# top.net
KiCad netlist of a schematic drawn in Altium Designer
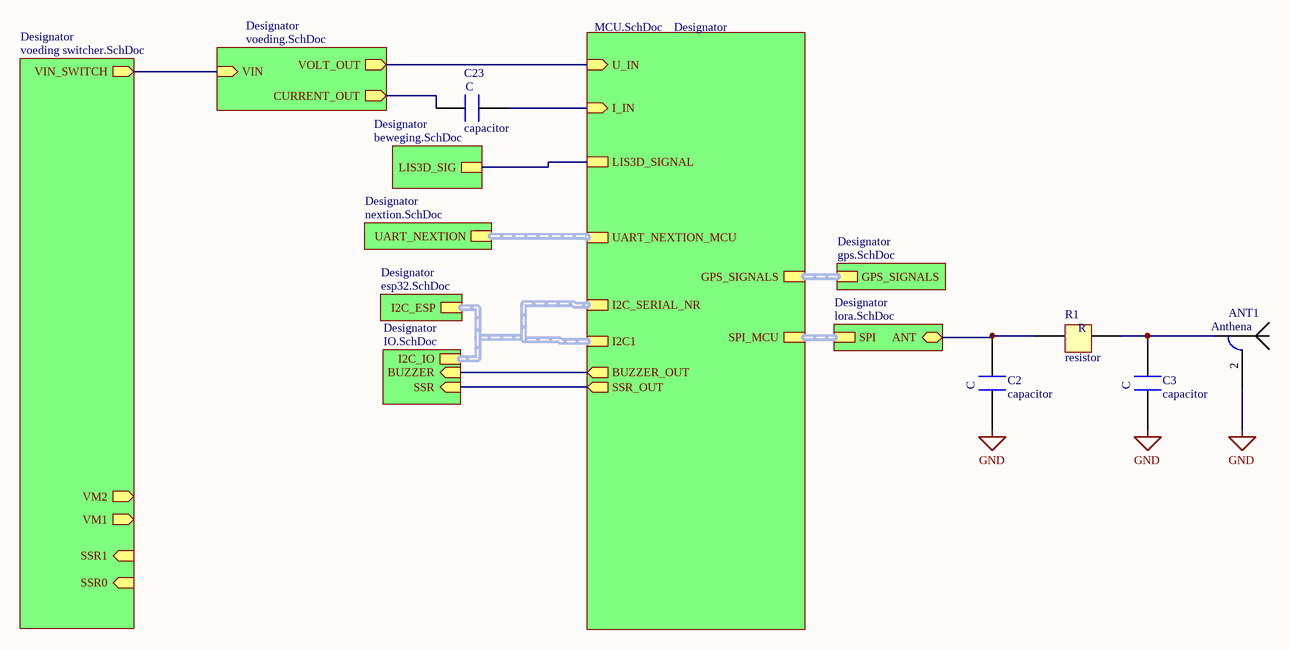
[diagram p0: top.SchDoc]

(export (version "E")
  (design (tool "Eeschema 10.0.6"))
  (components
    (comp (ref "ANT1")
      (value "Anthena")
      (footprint "sma connector")
      (libsource (lib "pasives") (part "Anthena"))
    )
    (comp (ref "C2") (value "capacitor") (footprint "0603") (libsource (lib "") (part "capacitor_1")))
    (comp (ref "C3") (value "capacitor") (footprint "0603") (libsource (lib "") (part "capacitor_1")))
    (comp (ref "C23") (value "capacitor") (footprint "0603") (libsource (lib "pasives") (part "capacitor")))
    (comp (ref "R1") (value "resistor") (footprint "0603") (libsource (lib "pasives") (part "resistor")))
  )
  (nets
    (net (code "1") (name "/ANT") (class "Default")
      (node (ref "C2") (pin "1") (pinfunction "1_1") (pintype "passive"))
      (node (ref "R1") (pin "2") (pinfunction "2_2") (pintype "passive"))
    )
    (net (code "3") (name "/CURRENT_OUT") (class "Default")
      (node (ref "C23") (pin "2") (pinfunction "2_2") (pintype "passive"))
    )
    (net (code "6") (name "/I_IN") (class "Default")
      (node (ref "C23") (pin "1") (pinfunction "1_1") (pintype "passive"))
    )
    (net (code "17") (name "GND") (class "Default")
      (node (ref "ANT1") (pin "2") (pinfunction "2_2") (pintype "passive"))
      (node (ref "C2") (pin "2") (pinfunction "2_2") (pintype "passive"))
      (node (ref "C3") (pin "2") (pinfunction "2_2") (pintype "passive"))
    )
    (net (code "18") (name "Net-(ANT1-Pad1)") (class "Default")
      (node (ref "ANT1") (pin "1") (pinfunction "1_1") (pintype "passive"))
      (node (ref "C3") (pin "1") (pinfunction "1_1") (pintype "passive"))
      (node (ref "R1") (pin "1") (pinfunction "1_1") (pintype "passive"))
    )
  )
)
